# 9_-_UV_OV_Protection.net
KiCad netlist of a schematic drawn in Altium Designer
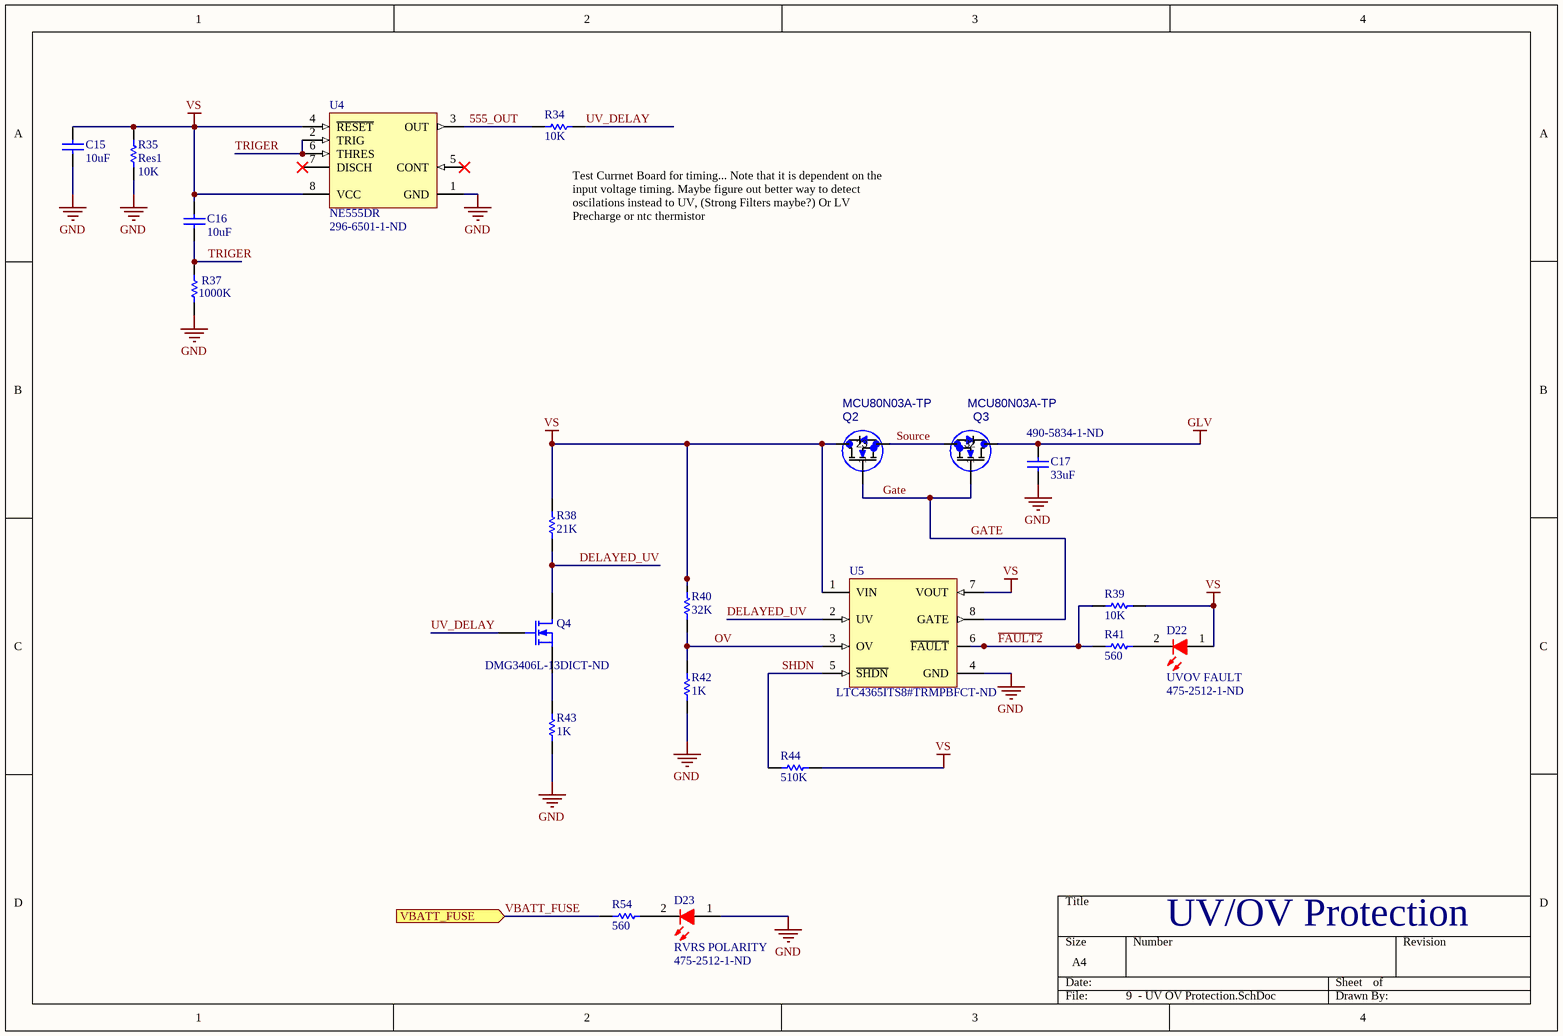
[diagram p0: 9  - UV OV Protection.SchDoc]

(export (version "E")
  (design (tool "Eeschema 10.0.6"))
  (components
    (comp (ref "C15")
      (value "10uF")
      (footprint "1608[0603]")
      (description "Capacitor (Semiconductor SIM Model)")
      (fields (field (name "Comment") "Cap Semi") (field (name "PUBLISHER") "Altium Limited"))
      (libsource (lib "Miscellaneous Devices") (part "Cap Semi"))
    )
    (comp (ref "C16")
      (value "10uF")
      (footprint "1608[0603]")
      (description "Capacitor (Semiconductor SIM Model)")
      (fields (field (name "Comment") "Cap Semi") (field (name "PUBLISHER") "Altium Limited"))
      (libsource (lib "Miscellaneous Devices") (part "Cap Semi"))
    )
    (comp (ref "C17")
      (value "33uF")
      (footprint "2J-Lead 6.1 x 5.3")
      (description "Capacitor (Semiconductor SIM Model)")
      (fields
        (field (name "SUPPLIER PART NUMBER 1") "490-5834-1-ND")
        (field (name "Comment") "Cap Semi")
        (field (name "PUBLISHER") "Altium Limited")
      )
      (libsource (lib "Miscellaneous Devices") (part "Cap Semi"))
    )
    (comp (ref "D22")
      (value "UVOV FAULT")
      (footprint "TOSH-0603LED_RED_V")
      (description "LED, Red 0603 (1608) 63mCd")
      (fields
        (field (name "MANUFACTURER") "Toshiba")
        (field (name "PARTNUMBER") "TLSU1008A(T04)")
        (field (name "SUPPLIER PART NUMBER 1") "475-2512-1-ND")
      )
      (libsource (lib "Altium Content Vault") (part "CMP-0444-00001-1"))
    )
    (comp (ref "D23")
      (value "RVRS POLARITY")
      (footprint "TOSH-0603LED_RED_V")
      (description "LED, Red 0603 (1608) 63mCd")
      (fields
        (field (name "MANUFACTURER") "Toshiba")
        (field (name "PARTNUMBER") "TLSU1008A(T04)")
        (field (name "SUPPLIER PART NUMBER 1") "475-2512-1-ND")
      )
      (libsource (lib "Altium Content Vault") (part "CMP-0444-00001-1"))
    )
    (comp (ref "Q2")
      (value "MCU80N03A-TP")
      (footprint "MCU80N_MCE")
      (fields (field (name "COPYRIGHT") "Copyright (C) 2022 Ultra Librarian. All rights reserved."))
      (libsource (lib "ACB_lib") (part "MCU80N03A-TP"))
    )
    (comp (ref "Q3")
      (value "MCU80N03A-TP")
      (footprint "MCU80N_MCE")
      (fields (field (name "COPYRIGHT") "Copyright (C) 2022 Ultra Librarian. All rights reserved."))
      (libsource (lib "ACB_lib") (part "MCU80N03A-TP"))
    )
    (comp (ref "Q4")
      (value "~")
      (footprint "SOT-23_N")
      (description "N-Channel MOSFET")
      (fields
        (field (name "MANUFACTURER") "Infineon Technologies")
        (field (name "MANUFACTURER PART NUMBER") "IPD075N03L G")
        (field (name "SUPPLIER PART NUMBER 1") "DMG3406L-13DICT-ND")
        (field (name "PUBLISHER") "Altium Limited")
      )
      (libsource (lib "Miscellaneous Devices") (part "MOSFET-N"))
    )
    (comp (ref "R34")
      (value "10K")
      (footprint "RESC0603(1608)_L")
      (description "0603 (1608 Metric) Chip Resistor")
      (libsource (lib "Altium Content Vault") (part "RES_3"))
    )
    (comp (ref "R35")
      (value "Res1")
      (footprint "1608[0603]")
      (description "RES SMD 10K OHM 5% 1/4W 0603")
      (fields
        (field (name "ALTIUM_VALUE") "10K")
        (field (name "MANUFACTURER") "Rohm Semiconductor")
        (field (name "MANUFACTURER PART NUMBER") "ESR03EZPJ103")
        (field (name "PUBLISHER") "Altium Limited")
      )
      (libsource (lib "Miscellaneous Devices") (part "Res1"))
    )
    (comp (ref "R37")
      (value "1000K")
      (footprint "RESC0603(1608)_L")
      (description "0603 (1608 Metric) Chip Resistor")
      (libsource (lib "Altium Content Vault") (part "RES_3"))
    )
    (comp (ref "R38")
      (value "21K")
      (footprint "RESC0603(1608)_L")
      (description "0603 (1608 Metric) Chip Resistor")
      (libsource (lib "Altium Content Vault") (part "RES_3"))
    )
    (comp (ref "R39")
      (value "10K")
      (footprint "RESC0603(1608)_L")
      (description "0603 (1608 Metric) Chip Resistor")
      (libsource (lib "Altium Content Vault") (part "RES_3"))
    )
    (comp (ref "R40")
      (value "32K")
      (footprint "RESC0603(1608)_L")
      (description "0603 (1608 Metric) Chip Resistor")
      (libsource (lib "Altium Content Vault") (part "RES_3"))
    )
    (comp (ref "R41")
      (value "560")
      (footprint "RESC0603(1608)_L")
      (description "0603 (1608 Metric) Chip Resistor")
      (libsource (lib "Altium Content Vault") (part "RES_3"))
    )
    (comp (ref "R42")
      (value "1K")
      (footprint "RESC0603(1608)_L")
      (description "0603 (1608 Metric) Chip Resistor")
      (libsource (lib "Altium Content Vault") (part "RES_3"))
    )
    (comp (ref "R43")
      (value "1K")
      (footprint "RESC0603(1608)_L")
      (description "0603 (1608 Metric) Chip Resistor")
      (libsource (lib "Altium Content Vault") (part "RES_3"))
    )
    (comp (ref "R44")
      (value "510K")
      (footprint "RESC0603(1608)_L")
      (description "0603 (1608 Metric) Chip Resistor")
      (libsource (lib "Altium Content Vault") (part "RES_3"))
    )
    (comp (ref "R54")
      (value "560")
      (footprint "RESC0603(1608)_L")
      (description "0603 (1608 Metric) Chip Resistor")
      (libsource (lib "Altium Content Vault") (part "RES_3"))
    )
    (comp (ref "U4")
      (value "NE555DR")
      (footprint "D0008A_M")
      (fields (field (name "SUPPLIER PART NUMBER 1") "296-6501-1-ND"))
      (libsource (lib "Altium Content Vault") (part "CMP-1685-00007-1"))
    )
    (comp (ref "U5")
      (value "LTC4365ITS8#TRMPBF")
      (footprint "LT-TS8-8-TSOT-23_V")
      (fields
        (field (name "MANUFACTURER") "Linear Technology")
        (field (name "SUPPLIER PART NUMBER 1") "LTC4365ITS8#TRMPBFCT-ND")
      )
      (libsource (lib "Altium Content Vault") (part "LT-LTC4365-TS8-8"))
    )
  )
  (nets
    (net (code "1") (name "/555_OUT") (class "Default")
      (node (ref "R34") (pin "1") (pinfunction "1_1") (pintype "passive"))
      (node (ref "U4") (pin "3") (pinfunction "OUT_3") (pintype "output"))
    )
    (net (code "2") (name "/DELAYED_UV") (class "Default")
      (node (ref "Q4") (pin "3") (pinfunction "D_3") (pintype "passive"))
      (node (ref "R38") (pin "2") (pinfunction "2_2") (pintype "passive"))
      (node (ref "U5") (pin "2") (pinfunction "UV_2") (pintype "input"))
    )
    (net (code "3") (name "/GATE") (class "Default")
      (node (ref "Q2") (pin "1") (pinfunction "1_1") (pintype "passive"))
      (node (ref "Q3") (pin "1") (pinfunction "1_1") (pintype "passive"))
      (node (ref "U5") (pin "8") (pinfunction "GATE_8") (pintype "output"))
    )
    (net (code "4") (name "/OV") (class "Default")
      (node (ref "R40") (pin "1") (pinfunction "1_1") (pintype "passive"))
      (node (ref "R42") (pin "2") (pinfunction "2_2") (pintype "passive"))
      (node (ref "U5") (pin "3") (pinfunction "OV_3") (pintype "input"))
    )
    (net (code "5") (name "/SHDN") (class "Default")
      (node (ref "R44") (pin "2") (pinfunction "2_2") (pintype "passive"))
      (node (ref "U5") (pin "5") (pinfunction "~{SHDN}_5") (pintype "input"))
    )
    (net (code "6") (name "/Source") (class "Default")
      (node (ref "Q2") (pin "3") (pinfunction "3_3") (pintype "passive"))
      (node (ref "Q3") (pin "3") (pinfunction "3_3") (pintype "passive"))
    )
    (net (code "7") (name "/TRIGER") (class "Default")
      (node (ref "C16") (pin "1") (pinfunction "1_1") (pintype "passive"))
      (node (ref "R37") (pin "2") (pinfunction "2_2") (pintype "passive"))
      (node (ref "U4") (pin "2") (pinfunction "TRIG_2") (pintype "input"))
      (node (ref "U4") (pin "6") (pinfunction "THRES_6") (pintype "input"))
    )
    (net (code "8") (name "/UV_DELAY") (class "Default")
      (node (ref "Q4") (pin "1") (pinfunction "G_1") (pintype "passive"))
      (node (ref "R34") (pin "2") (pinfunction "2_2") (pintype "passive"))
    )
    (net (code "9") (name "/VBATT_FUSE") (class "Default")
      (node (ref "R54") (pin "1") (pinfunction "1_1") (pintype "passive"))
    )
    (net (code "10") (name "/~{FAULT2}") (class "Default")
      (node (ref "R39") (pin "2") (pinfunction "2_2") (pintype "passive"))
      (node (ref "R41") (pin "1") (pinfunction "1_1") (pintype "passive"))
      (node (ref "U5") (pin "6") (pinfunction "~{FAULT}_6") (pintype "open_collector"))
    )
    (net (code "11") (name "GLV") (class "Default")
      (node (ref "C17") (pin "1") (pinfunction "1_1") (pintype "passive"))
      (node (ref "Q3") (pin "2") (pinfunction "2_2") (pintype "passive"))
    )
    (net (code "12") (name "GND") (class "Default")
      (node (ref "C15") (pin "1") (pinfunction "1_1") (pintype "passive"))
      (node (ref "C17") (pin "2") (pinfunction "2_2") (pintype "passive"))
      (node (ref "D23") (pin "1") (pinfunction "A_1") (pintype "passive"))
      (node (ref "R35") (pin "1") (pinfunction "1_1") (pintype "passive"))
      (node (ref "R37") (pin "1") (pinfunction "1_1") (pintype "passive"))
      (node (ref "R42") (pin "1") (pinfunction "1_1") (pintype "passive"))
      (node (ref "R43") (pin "2") (pinfunction "2_2") (pintype "passive"))
      (node (ref "U4") (pin "1") (pinfunction "GND_1") (pintype "power_in"))
      (node (ref "U5") (pin "4") (pinfunction "GND_4") (pintype "power_in"))
    )
    (net (code "13") (name "Net-(D22-K)") (class "Default")
      (node (ref "D22") (pin "2") (pinfunction "K_2") (pintype "passive"))
      (node (ref "R41") (pin "2") (pinfunction "2_2") (pintype "passive"))
    )
    (net (code "14") (name "Net-(D23-K)") (class "Default")
      (node (ref "D23") (pin "2") (pinfunction "K_2") (pintype "passive"))
      (node (ref "R54") (pin "2") (pinfunction "2_2") (pintype "passive"))
    )
    (net (code "15") (name "Net-(Q4-S)") (class "Default")
      (node (ref "Q4") (pin "2") (pinfunction "S_2") (pintype "passive"))
      (node (ref "R43") (pin "1") (pinfunction "1_1") (pintype "passive"))
    )
    (net (code "16") (name "VS") (class "Default")
      (node (ref "C15") (pin "2") (pinfunction "2_2") (pintype "passive"))
      (node (ref "C16") (pin "2") (pinfunction "2_2") (pintype "passive"))
      (node (ref "D22") (pin "1") (pinfunction "A_1") (pintype "passive"))
      (node (ref "Q2") (pin "2") (pinfunction "2_2") (pintype "passive"))
      (node (ref "R35") (pin "2") (pinfunction "2_2") (pintype "passive"))
      (node (ref "R38") (pin "1") (pinfunction "1_1") (pintype "passive"))
      (node (ref "R39") (pin "1") (pinfunction "1_1") (pintype "passive"))
      (node (ref "R40") (pin "2") (pinfunction "2_2") (pintype "passive"))
      (node (ref "R44") (pin "1") (pinfunction "1_1") (pintype "passive"))
      (node (ref "U4") (pin "4") (pinfunction "~{RESET}_4") (pintype "input"))
      (node (ref "U4") (pin "8") (pinfunction "VCC_8") (pintype "power_in"))
      (node (ref "U5") (pin "1") (pinfunction "VIN_1") (pintype "power_in"))
      (node (ref "U5") (pin "7") (pinfunction "VOUT_7") (pintype "input"))
    )
    (net (code "17") (name "unconnected-(U4-CONT-Pad5)") (class "Default")
      (node (ref "U4") (pin "5") (pinfunction "CONT_5") (pintype "input+no_connect"))
    )
    (net (code "18") (name "unconnected-(U4-DISCH-Pad7)") (class "Default")
      (node (ref "U4") (pin "7") (pinfunction "DISCH_7") (pintype "open_collector+no_connect"))
    )
  )
)
